# v0_2_0.net
KiCad netlist of a schematic drawn in EAGLE
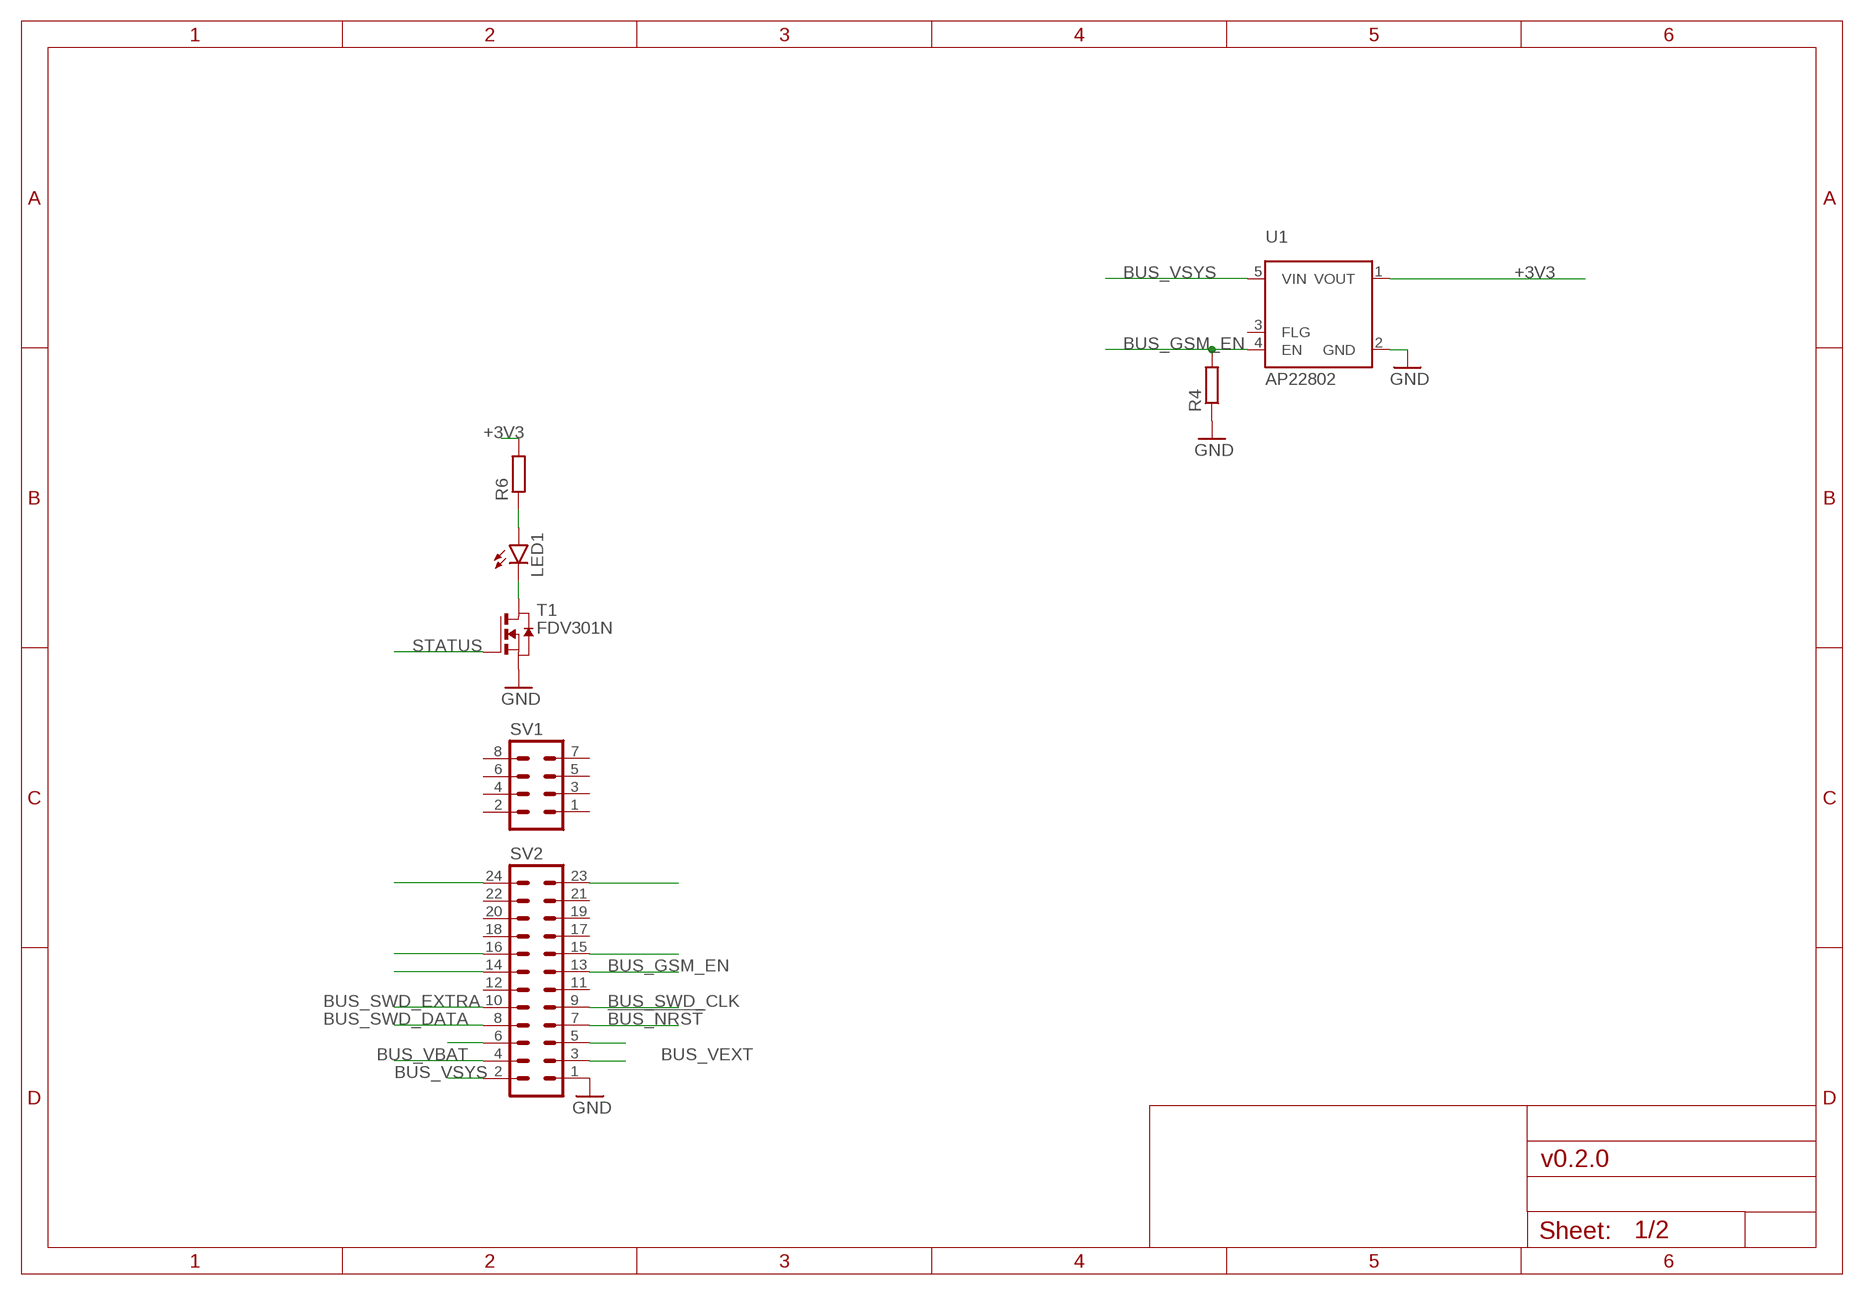
[diagram p0: schematic, sheet 1]
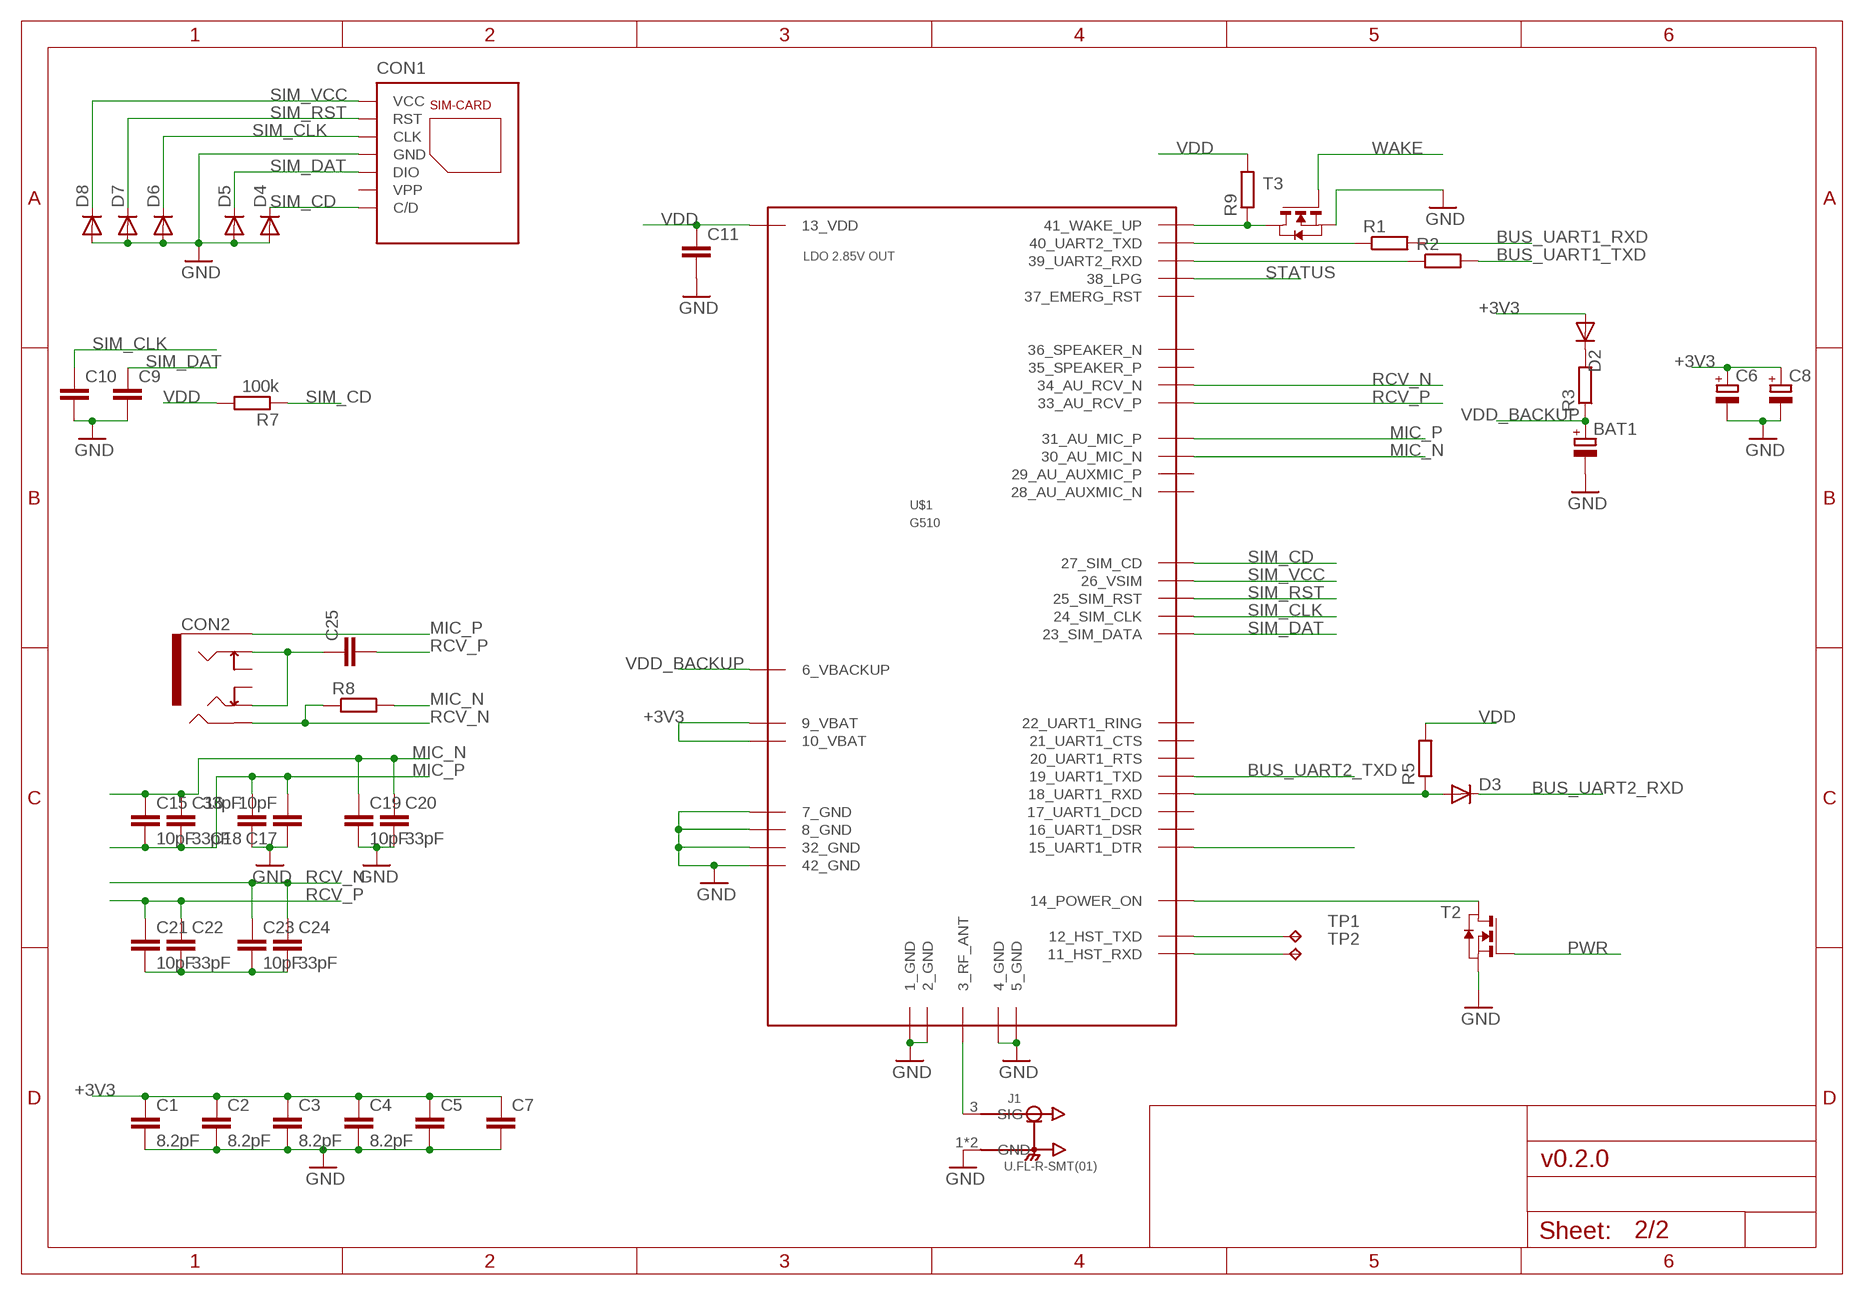
[diagram p1: schematic, sheet 2]

(export (version "E")
  (design (tool "Eeschema 10.0.6"))
  (components
    (comp (ref "BAT1")
      (value "DCK-3R3E224U-E")
      (footprint "eagle-import:621")
      (libsource (lib "eagle-import") (part "DCK-3R3E224U-E"))
    )
    (comp (ref "C1")
      (value "8.2pF")
      (footprint "eagle-import:C0402")
      (libsource (lib "eagle-import") (part "C-EUC0402"))
    )
    (comp (ref "C2")
      (value "8.2pF")
      (footprint "eagle-import:C0402")
      (libsource (lib "eagle-import") (part "C-EUC0402"))
    )
    (comp (ref "C3")
      (value "8.2pF")
      (footprint "eagle-import:C0402")
      (libsource (lib "eagle-import") (part "C-EUC0402"))
    )
    (comp (ref "C4")
      (value "8.2pF")
      (footprint "eagle-import:C0402")
      (libsource (lib "eagle-import") (part "C-EUC0402"))
    )
    (comp (ref "C5")
      (value "C-EUC0603")
      (footprint "eagle-import:C0603")
      (libsource (lib "eagle-import") (part "C-EUC0603"))
    )
    (comp (ref "C6")
      (value "CPOL-EUSMCC")
      (footprint "eagle-import:SMC_C")
      (libsource (lib "eagle-import") (part "CPOL-EUSMCC"))
    )
    (comp (ref "C7")
      (value "C-EUC0603")
      (footprint "eagle-import:C0603")
      (libsource (lib "eagle-import") (part "C-EUC0603"))
    )
    (comp (ref "C8")
      (value "CPOL-EUSMCC")
      (footprint "eagle-import:SMC_C")
      (libsource (lib "eagle-import") (part "CPOL-EUSMCC"))
    )
    (comp (ref "C9")
      (value "C-EUC0402")
      (footprint "eagle-import:C0402")
      (libsource (lib "eagle-import") (part "C-EUC0402"))
    )
    (comp (ref "C10")
      (value "C-EUC0402")
      (footprint "eagle-import:C0402")
      (libsource (lib "eagle-import") (part "C-EUC0402"))
    )
    (comp (ref "C11")
      (value "C-EUC0402")
      (footprint "eagle-import:C0402")
      (libsource (lib "eagle-import") (part "C-EUC0402"))
    )
    (comp (ref "C15")
      (value "10pF")
      (footprint "eagle-import:C0402")
      (libsource (lib "eagle-import") (part "C-EUC0402"))
    )
    (comp (ref "C16")
      (value "33pF")
      (footprint "eagle-import:C0402")
      (libsource (lib "eagle-import") (part "C-EUC0402"))
    )
    (comp (ref "C17")
      (value "10pF")
      (footprint "eagle-import:C0402")
      (libsource (lib "eagle-import") (part "C-EUC0402"))
    )
    (comp (ref "C18")
      (value "33pF")
      (footprint "eagle-import:C0402")
      (libsource (lib "eagle-import") (part "C-EUC0402"))
    )
    (comp (ref "C19")
      (value "10pF")
      (footprint "eagle-import:C0402")
      (libsource (lib "eagle-import") (part "C-EUC0402"))
    )
    (comp (ref "C20")
      (value "33pF")
      (footprint "eagle-import:C0402")
      (libsource (lib "eagle-import") (part "C-EUC0402"))
    )
    (comp (ref "C21")
      (value "10pF")
      (footprint "eagle-import:C0402")
      (libsource (lib "eagle-import") (part "C-EUC0402"))
    )
    (comp (ref "C22")
      (value "33pF")
      (footprint "eagle-import:C0402")
      (libsource (lib "eagle-import") (part "C-EUC0402"))
    )
    (comp (ref "C23")
      (value "10pF")
      (footprint "eagle-import:C0402")
      (libsource (lib "eagle-import") (part "C-EUC0402"))
    )
    (comp (ref "C24")
      (value "33pF")
      (footprint "eagle-import:C0402")
      (libsource (lib "eagle-import") (part "C-EUC0402"))
    )
    (comp (ref "C25")
      (value "C-EUC0603")
      (footprint "eagle-import:C0603")
      (libsource (lib "eagle-import") (part "C-EUC0603"))
    )
    (comp (ref "CON1")
      (value "115Q-BCA0")
      (footprint "eagle-import:115Q")
      (libsource (lib "eagle-import") (part "115Q-BCA0"))
    )
    (comp (ref "CON2")
      (value "1503-21")
      (footprint "eagle-import:150321")
      (libsource (lib "eagle-import") (part "1503-21"))
    )
    (comp (ref "D2")
      (value "DIODE-SOD323-R")
      (footprint "eagle-import:SOD323-R")
      (libsource (lib "eagle-import") (part "DIODE-SOD323-R"))
    )
    (comp (ref "D3")
      (value "DIODE-SOD323-R")
      (footprint "eagle-import:SOD323-R")
      (libsource (lib "eagle-import") (part "DIODE-SOD323-R"))
    )
    (comp (ref "D4")
      (value "DIODE-SOD323-R")
      (footprint "eagle-import:SOD323-R")
      (libsource (lib "eagle-import") (part "DIODE-SOD323-R"))
    )
    (comp (ref "D5")
      (value "DIODE-SOD323-R")
      (footprint "eagle-import:SOD323-R")
      (libsource (lib "eagle-import") (part "DIODE-SOD323-R"))
    )
    (comp (ref "D6")
      (value "DIODE-SOD323-R")
      (footprint "eagle-import:SOD323-R")
      (libsource (lib "eagle-import") (part "DIODE-SOD323-R"))
    )
    (comp (ref "D7")
      (value "DIODE-SOD323-R")
      (footprint "eagle-import:SOD323-R")
      (libsource (lib "eagle-import") (part "DIODE-SOD323-R"))
    )
    (comp (ref "D8")
      (value "DIODE-SOD323-R")
      (footprint "eagle-import:SOD323-R")
      (libsource (lib "eagle-import") (part "DIODE-SOD323-R"))
    )
    (comp (ref "J1")
      (value "U.FL-R-SMT(01)")
      (footprint "eagle-import:HRS_U.FL-R-SMT(01)")
      (fields (field (name "MF") "Hirose") (field (name "MP") "U.FL-R-SMT_01_"))
      (libsource (lib "eagle-import") (part "U.FL-R-SMT(01)"))
    )
    (comp (ref "R1")
      (value "R-EU_R0402")
      (footprint "eagle-import:R0402")
      (libsource (lib "eagle-import") (part "R-EU_R0402"))
    )
    (comp (ref "R2")
      (value "R-EU_R0402")
      (footprint "eagle-import:R0402")
      (libsource (lib "eagle-import") (part "R-EU_R0402"))
    )
    (comp (ref "R3")
      (value "R-EU_R0402")
      (footprint "eagle-import:R0402")
      (libsource (lib "eagle-import") (part "R-EU_R0402"))
    )
    (comp (ref "R5")
      (value "R-EU_R0402")
      (footprint "eagle-import:R0402")
      (libsource (lib "eagle-import") (part "R-EU_R0402"))
    )
    (comp (ref "R7")
      (value "100k")
      (footprint "eagle-import:R0402")
      (libsource (lib "eagle-import") (part "R-EU_R0402"))
    )
    (comp (ref "R8")
      (value "R-EU_R0402")
      (footprint "eagle-import:R0402")
      (libsource (lib "eagle-import") (part "R-EU_R0402"))
    )
    (comp (ref "R9")
      (value "R-EU_R0402")
      (footprint "eagle-import:R0402")
      (libsource (lib "eagle-import") (part "R-EU_R0402"))
    )
    (comp (ref "T2")
      (value "NMOSSOT23")
      (footprint "eagle-import:SOT-23")
      (libsource (lib "eagle-import") (part "NMOSSOT23"))
    )
    (comp (ref "T3")
      (value "NMOSSOT23")
      (footprint "eagle-import:SOT-23")
      (libsource (lib "eagle-import") (part "NMOSSOT23"))
    )
    (comp (ref "TP1")
      (value "TPB1,27")
      (footprint "eagle-import:B1,27")
      (libsource (lib "eagle-import") (part "TPB1,27"))
    )
    (comp (ref "TP2")
      (value "TPB1,27")
      (footprint "eagle-import:B1,27")
      (libsource (lib "eagle-import") (part "TPB1,27"))
    )
    (comp (ref "U$1")
      (value "G510")
      (footprint "eagle-import:G510")
      (libsource (lib "eagle-import") (part "G510"))
    )
    (comp (ref "LED1")
      (value "LEDCHIP-LED0603")
      (footprint "eagle-import:CHIP-LED0603")
      (libsource (lib "eagle-import") (part "LEDCHIP-LED0603"))
    )
    (comp (ref "R4")
      (value "R-EU_R0402")
      (footprint "eagle-import:R0402")
      (libsource (lib "eagle-import") (part "R-EU_R0402"))
    )
    (comp (ref "R6")
      (value "R-EU_R0402")
      (footprint "eagle-import:R0402")
      (libsource (lib "eagle-import") (part "R-EU_R0402"))
    )
    (comp (ref "SV1")
      (value "MA04-2")
      (footprint "eagle-import:MA04-2")
      (libsource (lib "eagle-import") (part "MA04-2"))
    )
    (comp (ref "SV2")
      (value "MA12-2")
      (footprint "eagle-import:MA12-2")
      (libsource (lib "eagle-import") (part "MA12-2"))
    )
    (comp (ref "T1")
      (value "FDV301N")
      (footprint "eagle-import:SOT-23")
      (libsource (lib "eagle-import") (part "NMOSSOT23"))
    )
    (comp (ref "U1")
      (value "AP22802")
      (footprint "eagle-import:SOT25")
      (libsource (lib "eagle-import") (part "AP22802"))
    )
  )
  (nets
    (net (code "1") (name "+3V3") (class "Default")
      (node (ref "C1") (pin "1") (pinfunction "1_1") (pintype "passive"))
      (node (ref "C2") (pin "1") (pinfunction "1_1") (pintype "passive"))
      (node (ref "C3") (pin "1") (pinfunction "1_1") (pintype "passive"))
      (node (ref "C4") (pin "1") (pinfunction "1_1") (pintype "passive"))
      (node (ref "C5") (pin "1") (pinfunction "1_1") (pintype "passive"))
      (node (ref "C6") (pin "+") (pinfunction "+_+") (pintype "passive"))
      (node (ref "C7") (pin "1") (pinfunction "1_1") (pintype "passive"))
      (node (ref "C8") (pin "+") (pinfunction "+_+") (pintype "passive"))
      (node (ref "D2") (pin "A") (pinfunction "A_A") (pintype "passive"))
      (node (ref "R6") (pin "2") (pinfunction "2_2") (pintype "passive"))
      (node (ref "U$1") (pin "10_VBAT") (pinfunction "10_VBAT_10_VBAT") (pintype "power_in"))
      (node (ref "U$1") (pin "9_VBAT") (pinfunction "9_VBAT_9_VBAT") (pintype "power_in"))
      (node (ref "U1") (pin "1") (pinfunction "VOUT_1") (pintype "bidirectional"))
    )
    (net (code "2") (name "BUS_GSM_EN") (class "Default")
      (node (ref "R4") (pin "2") (pinfunction "2_2") (pintype "passive"))
      (node (ref "SV2") (pin "13") (pinfunction "13_13") (pintype "passive"))
      (node (ref "U1") (pin "4") (pinfunction "EN_4") (pintype "bidirectional"))
    )
    (net (code "3") (name "BUS_SWD_CLK") (class "Default")
      (node (ref "SV2") (pin "9") (pinfunction "9_9") (pintype "passive"))
    )
    (net (code "4") (name "BUS_SWD_DATA") (class "Default")
      (node (ref "SV2") (pin "8") (pinfunction "8_8") (pintype "passive"))
    )
    (net (code "5") (name "BUS_SWD_EXTRA") (class "Default")
      (node (ref "SV2") (pin "10") (pinfunction "10_10") (pintype "passive"))
    )
    (net (code "6") (name "BUS_UART1_RXD") (class "Default")
      (node (ref "R1") (pin "2") (pinfunction "2_2") (pintype "passive"))
    )
    (net (code "7") (name "BUS_UART1_TXD") (class "Default")
      (node (ref "R2") (pin "2") (pinfunction "2_2") (pintype "passive"))
    )
    (net (code "8") (name "BUS_UART2_RXD") (class "Default")
      (node (ref "D3") (pin "C") (pinfunction "C_C") (pintype "passive"))
    )
    (net (code "9") (name "BUS_UART2_TXD") (class "Default")
      (node (ref "U$1") (pin "19_UART1_TXD") (pinfunction "19_UART1_TXD_19_UART1_TXD") (pintype "output"))
    )
    (net (code "10") (name "BUS_VBAT") (class "Default")
      (node (ref "SV2") (pin "4") (pinfunction "4_4") (pintype "passive"))
    )
    (net (code "11") (name "BUS_VEXT") (class "Default")
      (node (ref "SV2") (pin "3") (pinfunction "3_3") (pintype "passive"))
    )
    (net (code "12") (name "BUS_VSYS") (class "Default")
      (node (ref "SV2") (pin "2") (pinfunction "2_2") (pintype "passive"))
      (node (ref "U1") (pin "5") (pinfunction "VIN_5") (pintype "bidirectional"))
    )
    (net (code "13") (name "GND") (class "Default")
      (node (ref "BAT1") (pin "-") (pinfunction "-_-") (pintype "passive"))
      (node (ref "C1") (pin "2") (pinfunction "2_2") (pintype "passive"))
      (node (ref "C10") (pin "2") (pinfunction "2_2") (pintype "passive"))
      (node (ref "C11") (pin "2") (pinfunction "2_2") (pintype "passive"))
      (node (ref "C17") (pin "1") (pinfunction "1_1") (pintype "passive"))
      (node (ref "C18") (pin "1") (pinfunction "1_1") (pintype "passive"))
      (node (ref "C19") (pin "2") (pinfunction "2_2") (pintype "passive"))
      (node (ref "C2") (pin "2") (pinfunction "2_2") (pintype "passive"))
      (node (ref "C20") (pin "2") (pinfunction "2_2") (pintype "passive"))
      (node (ref "C3") (pin "2") (pinfunction "2_2") (pintype "passive"))
      (node (ref "C4") (pin "2") (pinfunction "2_2") (pintype "passive"))
      (node (ref "C5") (pin "2") (pinfunction "2_2") (pintype "passive"))
      (node (ref "C6") (pin "-") (pinfunction "-_-") (pintype "passive"))
      (node (ref "C7") (pin "2") (pinfunction "2_2") (pintype "passive"))
      (node (ref "C8") (pin "-") (pinfunction "-_-") (pintype "passive"))
      (node (ref "C9") (pin "2") (pinfunction "2_2") (pintype "passive"))
      (node (ref "CON1") (pin "GND1") (pinfunction "GND_GND1") (pintype "passive"))
      (node (ref "CON1") (pin "GND2") (pinfunction "GND_GND2") (pintype "passive"))
      (node (ref "CON1") (pin "GND3") (pinfunction "GND_GND3") (pintype "passive"))
      (node (ref "CON1") (pin "GND4") (pinfunction "GND_GND4") (pintype "passive"))
      (node (ref "CON1") (pin "P5") (pinfunction "GND_P5") (pintype "passive"))
      (node (ref "D4") (pin "A") (pinfunction "A_A") (pintype "passive"))
      (node (ref "D5") (pin "A") (pinfunction "A_A") (pintype "passive"))
      (node (ref "D6") (pin "A") (pinfunction "A_A") (pintype "passive"))
      (node (ref "D7") (pin "A") (pinfunction "A_A") (pintype "passive"))
      (node (ref "D8") (pin "A") (pinfunction "A_A") (pintype "passive"))
      (node (ref "J1") (pin "1") (pinfunction "GND_1") (pintype "passive"))
      (node (ref "J1") (pin "2") (pinfunction "GND_2") (pintype "passive"))
      (node (ref "R4") (pin "1") (pinfunction "1_1") (pintype "passive"))
      (node (ref "SV2") (pin "1") (pinfunction "1_1") (pintype "passive"))
      (node (ref "T1") (pin "2") (pinfunction "S_2") (pintype "passive"))
      (node (ref "T2") (pin "2") (pinfunction "S_2") (pintype "passive"))
      (node (ref "T3") (pin "2") (pinfunction "S_2") (pintype "passive"))
      (node (ref "U$1") (pin "1_GND") (pinfunction "1_GND_1_GND") (pintype "power_in"))
      (node (ref "U$1") (pin "2_GND") (pinfunction "2_GND_2_GND") (pintype "power_in"))
      (node (ref "U$1") (pin "32_GND") (pinfunction "32_GND_32_GND") (pintype "power_in"))
      (node (ref "U$1") (pin "42_GND") (pinfunction "42_GND_42_GND") (pintype "power_in"))
      (node (ref "U$1") (pin "4_GND") (pinfunction "4_GND_4_GND") (pintype "power_in"))
      (node (ref "U$1") (pin "5_GND") (pinfunction "5_GND_5_GND") (pintype "power_in"))
      (node (ref "U$1") (pin "7_GND") (pinfunction "7_GND_7_GND") (pintype "power_in"))
      (node (ref "U$1") (pin "8_GND") (pinfunction "8_GND_8_GND") (pintype "power_in"))
      (node (ref "U1") (pin "2") (pinfunction "GND_2") (pintype "bidirectional"))
    )
    (net (code "14") (name "MIC_N") (class "Default")
      (node (ref "C15") (pin "1") (pinfunction "1_1") (pintype "passive"))
      (node (ref "C16") (pin "1") (pinfunction "1_1") (pintype "passive"))
      (node (ref "C19") (pin "1") (pinfunction "1_1") (pintype "passive"))
      (node (ref "C20") (pin "1") (pinfunction "1_1") (pintype "passive"))
      (node (ref "R8") (pin "2") (pinfunction "2_2") (pintype "passive"))
      (node (ref "U$1") (pin "30_AU_MIC_N") (pinfunction "30_AU_MIC_N_30_AU_MIC_N") (pintype "bidirectional"))
    )
    (net (code "15") (name "MIC_P") (class "Default")
      (node (ref "C15") (pin "2") (pinfunction "2_2") (pintype "passive"))
      (node (ref "C16") (pin "2") (pinfunction "2_2") (pintype "passive"))
      (node (ref "C17") (pin "2") (pinfunction "2_2") (pintype "passive"))
      (node (ref "C18") (pin "2") (pinfunction "2_2") (pintype "passive"))
      (node (ref "CON2") (pin "1") (pinfunction "1_1") (pintype "bidirectional"))
      (node (ref "U$1") (pin "31_AU_MIC_P") (pinfunction "31_AU_MIC_P_31_AU_MIC_P") (pintype "bidirectional"))
    )
    (net (code "16") (name "Net-(C21-Pad2)") (class "Default")
      (node (ref "C21") (pin "2") (pinfunction "2_2") (pintype "passive"))
      (node (ref "C22") (pin "2") (pinfunction "2_2") (pintype "passive"))
      (node (ref "C23") (pin "2") (pinfunction "2_2") (pintype "passive"))
      (node (ref "C24") (pin "2") (pinfunction "2_2") (pintype "passive"))
    )
    (net (code "17") (name "Net-(C25-Pad1)") (class "Default")
      (node (ref "C25") (pin "1") (pinfunction "1_1") (pintype "passive"))
      (node (ref "CON2") (pin "3") (pinfunction "3_3") (pintype "bidirectional"))
      (node (ref "CON2") (pin "5") (pinfunction "5_5") (pintype "bidirectional"))
    )
    (net (code "18") (name "Net-(D2-PadC)") (class "Default")
      (node (ref "D2") (pin "C") (pinfunction "C_C") (pintype "passive"))
      (node (ref "R3") (pin "2") (pinfunction "2_2") (pintype "passive"))
    )
    (net (code "19") (name "Net-(D3-PadA)") (class "Default")
      (node (ref "D3") (pin "A") (pinfunction "A_A") (pintype "passive"))
      (node (ref "R5") (pin "1") (pinfunction "1_1") (pintype "passive"))
      (node (ref "U$1") (pin "18_UART1_RXD") (pinfunction "18_UART1_RXD_18_UART1_RXD") (pintype "input"))
    )
    (net (code "20") (name "Net-(J1-SIG)") (class "Default")
      (node (ref "J1") (pin "3") (pinfunction "SIG_3") (pintype "passive"))
      (node (ref "U$1") (pin "3_RF_ANT") (pinfunction "3_RF_ANT_3_RF_ANT") (pintype "bidirectional"))
    )
    (net (code "21") (name "Net-(LED1-PadA)") (class "Default")
      (node (ref "LED1") (pin "A") (pinfunction "A_A") (pintype "passive"))
      (node (ref "R6") (pin "1") (pinfunction "1_1") (pintype "passive"))
    )
    (net (code "22") (name "Net-(R1-Pad1)") (class "Default")
      (node (ref "R1") (pin "1") (pinfunction "1_1") (pintype "passive"))
      (node (ref "U$1") (pin "40_UART2_TXD") (pinfunction "40_UART2_TXD_40_UART2_TXD") (pintype "output"))
    )
    (net (code "23") (name "Net-(R2-Pad1)") (class "Default")
      (node (ref "R2") (pin "1") (pinfunction "1_1") (pintype "passive"))
      (node (ref "U$1") (pin "39_UART2_RXD") (pinfunction "39_UART2_RXD_39_UART2_RXD") (pintype "input"))
    )
    (net (code "24") (name "Net-(T1-D)") (class "Default")
      (node (ref "LED1") (pin "C") (pinfunction "C_C") (pintype "passive"))
      (node (ref "T1") (pin "1") (pinfunction "D_1") (pintype "passive"))
    )
    (net (code "25") (name "Net-(T2-D)") (class "Default")
      (node (ref "T2") (pin "1") (pinfunction "D_1") (pintype "passive"))
      (node (ref "U$1") (pin "14_POWER_ON") (pinfunction "14_POWER_ON_14_POWER_ON") (pintype "input"))
    )
    (net (code "26") (name "Net-(T3-D)") (class "Default")
      (node (ref "R9") (pin "1") (pinfunction "1_1") (pintype "passive"))
      (node (ref "T3") (pin "1") (pinfunction "D_1") (pintype "passive"))
      (node (ref "U$1") (pin "41_WAKE_UP") (pinfunction "41_WAKE_UP_41_WAKE_UP") (pintype "bidirectional"))
    )
    (net (code "27") (name "Net-(TP1-PadTP)") (class "Default")
      (node (ref "TP1") (pin "TP") (pinfunction "TP_TP") (pintype "input"))
      (node (ref "U$1") (pin "12_HST_TXD") (pinfunction "12_HST_TXD_12_HST_TXD") (pintype "output"))
    )
    (net (code "28") (name "Net-(U$1-11_HST_RXD)") (class "Default")
      (node (ref "TP2") (pin "TP") (pinfunction "TP_TP") (pintype "input"))
      (node (ref "U$1") (pin "11_HSTRXD") (pinfunction "11_HST_RXD_11_HSTRXD") (pintype "input"))
    )
    (net (code "29") (name "PWR") (class "Default")
      (node (ref "T2") (pin "3") (pinfunction "G_3") (pintype "passive"))
    )
    (net (code "30") (name "RCV_N") (class "Default")
      (node (ref "C23") (pin "1") (pinfunction "1_1") (pintype "passive"))
      (node (ref "C24") (pin "1") (pinfunction "1_1") (pintype "passive"))
      (node (ref "CON2") (pin "2") (pinfunction "2_2") (pintype "bidirectional"))
      (node (ref "R8") (pin "1") (pinfunction "1_1") (pintype "passive"))
      (node (ref "U$1") (pin "34_AU_RCV_N") (pinfunction "34_AU_RCV_N_34_AU_RCV_N") (pintype "bidirectional"))
    )
    (net (code "31") (name "RCV_P") (class "Default")
      (node (ref "C21") (pin "1") (pinfunction "1_1") (pintype "passive"))
      (node (ref "C22") (pin "1") (pinfunction "1_1") (pintype "passive"))
      (node (ref "C25") (pin "2") (pinfunction "2_2") (pintype "passive"))
      (node (ref "U$1") (pin "33_AU_RCV_P") (pinfunction "33_AU_RCV_P_33_AU_RCV_P") (pintype "bidirectional"))
    )
    (net (code "32") (name "SIM_CD") (class "Default")
      (node (ref "CON1") (pin "CD") (pinfunction "C/D_CD") (pintype "passive"))
      (node (ref "D4") (pin "C") (pinfunction "C_C") (pintype "passive"))
      (node (ref "R7") (pin "1") (pinfunction "1_1") (pintype "passive"))
      (node (ref "U$1") (pin "27_SIM_CD") (pinfunction "27_SIM_CD_27_SIM_CD") (pintype "bidirectional"))
    )
    (net (code "33") (name "SIM_CLK") (class "Default")
      (node (ref "C10") (pin "1") (pinfunction "1_1") (pintype "passive"))
      (node (ref "CON1") (pin "P3") (pinfunction "CLK_P3") (pintype "passive"))
      (node (ref "D6") (pin "C") (pinfunction "C_C") (pintype "passive"))
      (node (ref "U$1") (pin "24_SIM_CLK") (pinfunction "24_SIM_CLK_24_SIM_CLK") (pintype "bidirectional"))
    )
    (net (code "34") (name "SIM_DAT") (class "Default")
      (node (ref "C9") (pin "1") (pinfunction "1_1") (pintype "passive"))
      (node (ref "CON1") (pin "P7") (pinfunction "DIO_P7") (pintype "passive"))
      (node (ref "D5") (pin "C") (pinfunction "C_C") (pintype "passive"))
      (node (ref "U$1") (pin "23_SIM_DATA") (pinfunction "23_SIM_DATA_23_SIM_DATA") (pintype "bidirectional"))
    )
    (net (code "35") (name "SIM_RST") (class "Default")
      (node (ref "CON1") (pin "P2") (pinfunction "RST_P2") (pintype "passive"))
      (node (ref "D7") (pin "C") (pinfunction "C_C") (pintype "passive"))
      (node (ref "U$1") (pin "25_SIM_RST") (pinfunction "25_SIM_RST_25_SIM_RST") (pintype "bidirectional"))
    )
    (net (code "36") (name "SIM_VCC") (class "Default")
      (node (ref "CON1") (pin "P1") (pinfunction "VCC_P1") (pintype "passive"))
      (node (ref "D8") (pin "C") (pinfunction "C_C") (pintype "passive"))
      (node (ref "U$1") (pin "26_VSIM") (pinfunction "26_VSIM_26_VSIM") (pintype "bidirectional"))
    )
    (net (code "37") (name "STATUS") (class "Default")
      (node (ref "T1") (pin "3") (pinfunction "G_3") (pintype "passive"))
      (node (ref "U$1") (pin "38_LPG") (pinfunction "38_LPG_38_LPG") (pintype "output"))
    )
    (net (code "38") (name "VDD") (class "Default")
      (node (ref "C11") (pin "1") (pinfunction "1_1") (pintype "passive"))
      (node (ref "R5") (pin "2") (pinfunction "2_2") (pintype "passive"))
      (node (ref "R7") (pin "2") (pinfunction "2_2") (pintype "passive"))
      (node (ref "R9") (pin "2") (pinfunction "2_2") (pintype "passive"))
      (node (ref "U$1") (pin "13_VDD") (pinfunction "13_VDD_13_VDD") (pintype "power_in"))
    )
    (net (code "39") (name "VDD_BACKUP") (class "Default")
      (node (ref "BAT1") (pin "+") (pinfunction "+_+") (pintype "passive"))
      (node (ref "R3") (pin "1") (pinfunction "1_1") (pintype "passive"))
      (node (ref "U$1") (pin "6_VBACKUP") (pinfunction "6_VBACKUP_6_VBACKUP") (pintype "power_in"))
    )
    (net (code "40") (name "WAKE") (class "Default")
      (node (ref "T3") (pin "3") (pinfunction "G_3") (pintype "passive"))
    )
    (net (code "41") (name "unconnected-(CON1-VPP-PadP6)") (class "Default")
      (node (ref "CON1") (pin "P6") (pinfunction "VPP_P6") (pintype "passive"))
    )
    (net (code "42") (name "unconnected-(CON2-Pad4)") (class "Default")
      (node (ref "CON2") (pin "4") (pinfunction "4_4") (pintype "bidirectional"))
    )
    (net (code "43") (name "unconnected-(CON2-Pad6)") (class "Default")
      (node (ref "CON2") (pin "6") (pinfunction "6_6") (pintype "bidirectional"))
    )
    (net (code "44") (name "unconnected-(SV1-Pad1)") (class "Default")
      (node (ref "SV1") (pin "1") (pinfunction "1_1") (pintype "passive"))
    )
    (net (code "45") (name "unconnected-(SV1-Pad2)") (class "Default")
      (node (ref "SV1") (pin "2") (pinfunction "2_2") (pintype "passive"))
    )
    (net (code "46") (name "unconnected-(SV1-Pad3)") (class "Default")
      (node (ref "SV1") (pin "3") (pinfunction "3_3") (pintype "passive"))
    )
    (net (code "47") (name "unconnected-(SV1-Pad4)") (class "Default")
      (node (ref "SV1") (pin "4") (pinfunction "4_4") (pintype "passive"))
    )
    (net (code "48") (name "unconnected-(SV1-Pad5)") (class "Default")
      (node (ref "SV1") (pin "5") (pinfunction "5_5") (pintype "passive"))
    )
    (net (code "49") (name "unconnected-(SV1-Pad6)") (class "Default")
      (node (ref "SV1") (pin "6") (pinfunction "6_6") (pintype "passive"))
    )
    (net (code "50") (name "unconnected-(SV1-Pad7)") (class "Default")
      (node (ref "SV1") (pin "7") (pinfunction "7_7") (pintype "passive"))
    )
    (net (code "51") (name "unconnected-(SV1-Pad8)") (class "Default")
      (node (ref "SV1") (pin "8") (pinfunction "8_8") (pintype "passive"))
    )
    (net (code "52") (name "unconnected-(SV2-Pad5)") (class "Default")
      (node (ref "SV2") (pin "5") (pinfunction "5_5") (pintype "passive"))
    )
    (net (code "53") (name "unconnected-(SV2-Pad6)") (class "Default")
      (node (ref "SV2") (pin "6") (pinfunction "6_6") (pintype "passive"))
    )
    (net (code "54") (name "unconnected-(SV2-Pad11)") (class "Default")
      (node (ref "SV2") (pin "11") (pinfunction "11_11") (pintype "passive"))
    )
    (net (code "55") (name "unconnected-(SV2-Pad12)") (class "Default")
      (node (ref "SV2") (pin "12") (pinfunction "12_12") (pintype "passive"))
    )
    (net (code "56") (name "unconnected-(SV2-Pad14)") (class "Default")
      (node (ref "SV2") (pin "14") (pinfunction "14_14") (pintype "passive"))
    )
    (net (code "57") (name "unconnected-(SV2-Pad15)") (class "Default")
      (node (ref "SV2") (pin "15") (pinfunction "15_15") (pintype "passive"))
    )
    (net (code "58") (name "unconnected-(SV2-Pad16)") (class "Default")
      (node (ref "SV2") (pin "16") (pinfunction "16_16") (pintype "passive"))
    )
    (net (code "59") (name "unconnected-(SV2-Pad17)") (class "Default")
      (node (ref "SV2") (pin "17") (pinfunction "17_17") (pintype "passive"))
    )
    (net (code "60") (name "unconnected-(SV2-Pad18)") (class "Default")
      (node (ref "SV2") (pin "18") (pinfunction "18_18") (pintype "passive"))
    )
    (net (code "61") (name "unconnected-(SV2-Pad19)") (class "Default")
      (node (ref "SV2") (pin "19") (pinfunction "19_19") (pintype "passive"))
    )
    (net (code "62") (name "unconnected-(SV2-Pad20)") (class "Default")
      (node (ref "SV2") (pin "20") (pinfunction "20_20") (pintype "passive"))
    )
    (net (code "63") (name "unconnected-(SV2-Pad21)") (class "Default")
      (node (ref "SV2") (pin "21") (pinfunction "21_21") (pintype "passive"))
    )
    (net (code "64") (name "unconnected-(SV2-Pad22)") (class "Default")
      (node (ref "SV2") (pin "22") (pinfunction "22_22") (pintype "passive"))
    )
    (net (code "65") (name "unconnected-(SV2-Pad23)") (class "Default")
      (node (ref "SV2") (pin "23") (pinfunction "23_23") (pintype "passive"))
    )
    (net (code "66") (name "unconnected-(SV2-Pad24)") (class "Default")
      (node (ref "SV2") (pin "24") (pinfunction "24_24") (pintype "passive"))
    )
    (net (code "67") (name "unconnected-(U$1-Pad15_UART1_DTR)") (class "Default")
      (node (ref "U$1") (pin "15_UART1_DTR") (pinfunction "15_UART1_DTR_15_UART1_DTR") (pintype "bidirectional"))
    )
    (net (code "68") (name "unconnected-(U$1-Pad16_UART1_DSR)") (class "Default")
      (node (ref "U$1") (pin "16_UART1_DSR") (pinfunction "16_UART1_DSR_16_UART1_DSR") (pintype "bidirectional"))
    )
    (net (code "69") (name "unconnected-(U$1-Pad17_UART1_DCD)") (class "Default")
      (node (ref "U$1") (pin "17_UART1_DCD") (pinfunction "17_UART1_DCD_17_UART1_DCD") (pintype "bidirectional"))
    )
    (net (code "70") (name "unconnected-(U$1-Pad20_UART1_RTS)") (class "Default")
      (node (ref "U$1") (pin "20_UART1_RTS") (pinfunction "20_UART1_RTS_20_UART1_RTS") (pintype "bidirectional"))
    )
    (net (code "71") (name "unconnected-(U$1-Pad21_UART1_CTS)") (class "Default")
      (node (ref "U$1") (pin "21_UART1_CTS") (pinfunction "21_UART1_CTS_21_UART1_CTS") (pintype "bidirectional"))
    )
    (net (code "72") (name "unconnected-(U$1-Pad22_UART1_RING)") (class "Default")
      (node (ref "U$1") (pin "22_UART1_RING") (pinfunction "22_UART1_RING_22_UART1_RING") (pintype "bidirectional"))
    )
    (net (code "73") (name "unconnected-(U$1-Pad28_AU_AUXMIC_N)") (class "Default")
      (node (ref "U$1") (pin "28_AU_AUXMIC_N") (pinfunction "28_AU_AUXMIC_N_28_AU_AUXMIC_N") (pintype "bidirectional"))
    )
    (net (code "74") (name "unconnected-(U$1-Pad29_AU_AUXMIC_P)") (class "Default")
      (node (ref "U$1") (pin "29_AU_AUXMIC_P") (pinfunction "29_AU_AUXMIC_P_29_AU_AUXMIC_P") (pintype "bidirectional"))
    )
    (net (code "75") (name "unconnected-(U$1-Pad35_SPEAKER_P)") (class "Default")
      (node (ref "U$1") (pin "35_SPEAKER_P") (pinfunction "35_SPEAKER_P_35_SPEAKER_P") (pintype "bidirectional"))
    )
    (net (code "76") (name "unconnected-(U$1-Pad36_SPEAKER_N)") (class "Default")
      (node (ref "U$1") (pin "36_SPEAKER_N") (pinfunction "36_SPEAKER_N_36_SPEAKER_N") (pintype "bidirectional"))
    )
    (net (code "77") (name "unconnected-(U$1-Pad37_EMERG_RST)") (class "Default")
      (node (ref "U$1") (pin "37_EMERG_RST") (pinfunction "37_EMERG_RST_37_EMERG_RST") (pintype "input"))
    )
    (net (code "78") (name "unconnected-(U1-FLG-Pad3)") (class "Default")
      (node (ref "U1") (pin "3") (pinfunction "FLG_3") (pintype "bidirectional"))
    )
    (net (code "79") (name "~{BUS_NRST}") (class "Default")
      (node (ref "SV2") (pin "7") (pinfunction "7_7") (pintype "passive"))
    )
  )
)
